# Pwr_Brd1.net
KiCad netlist of a schematic drawn in Altium Designer
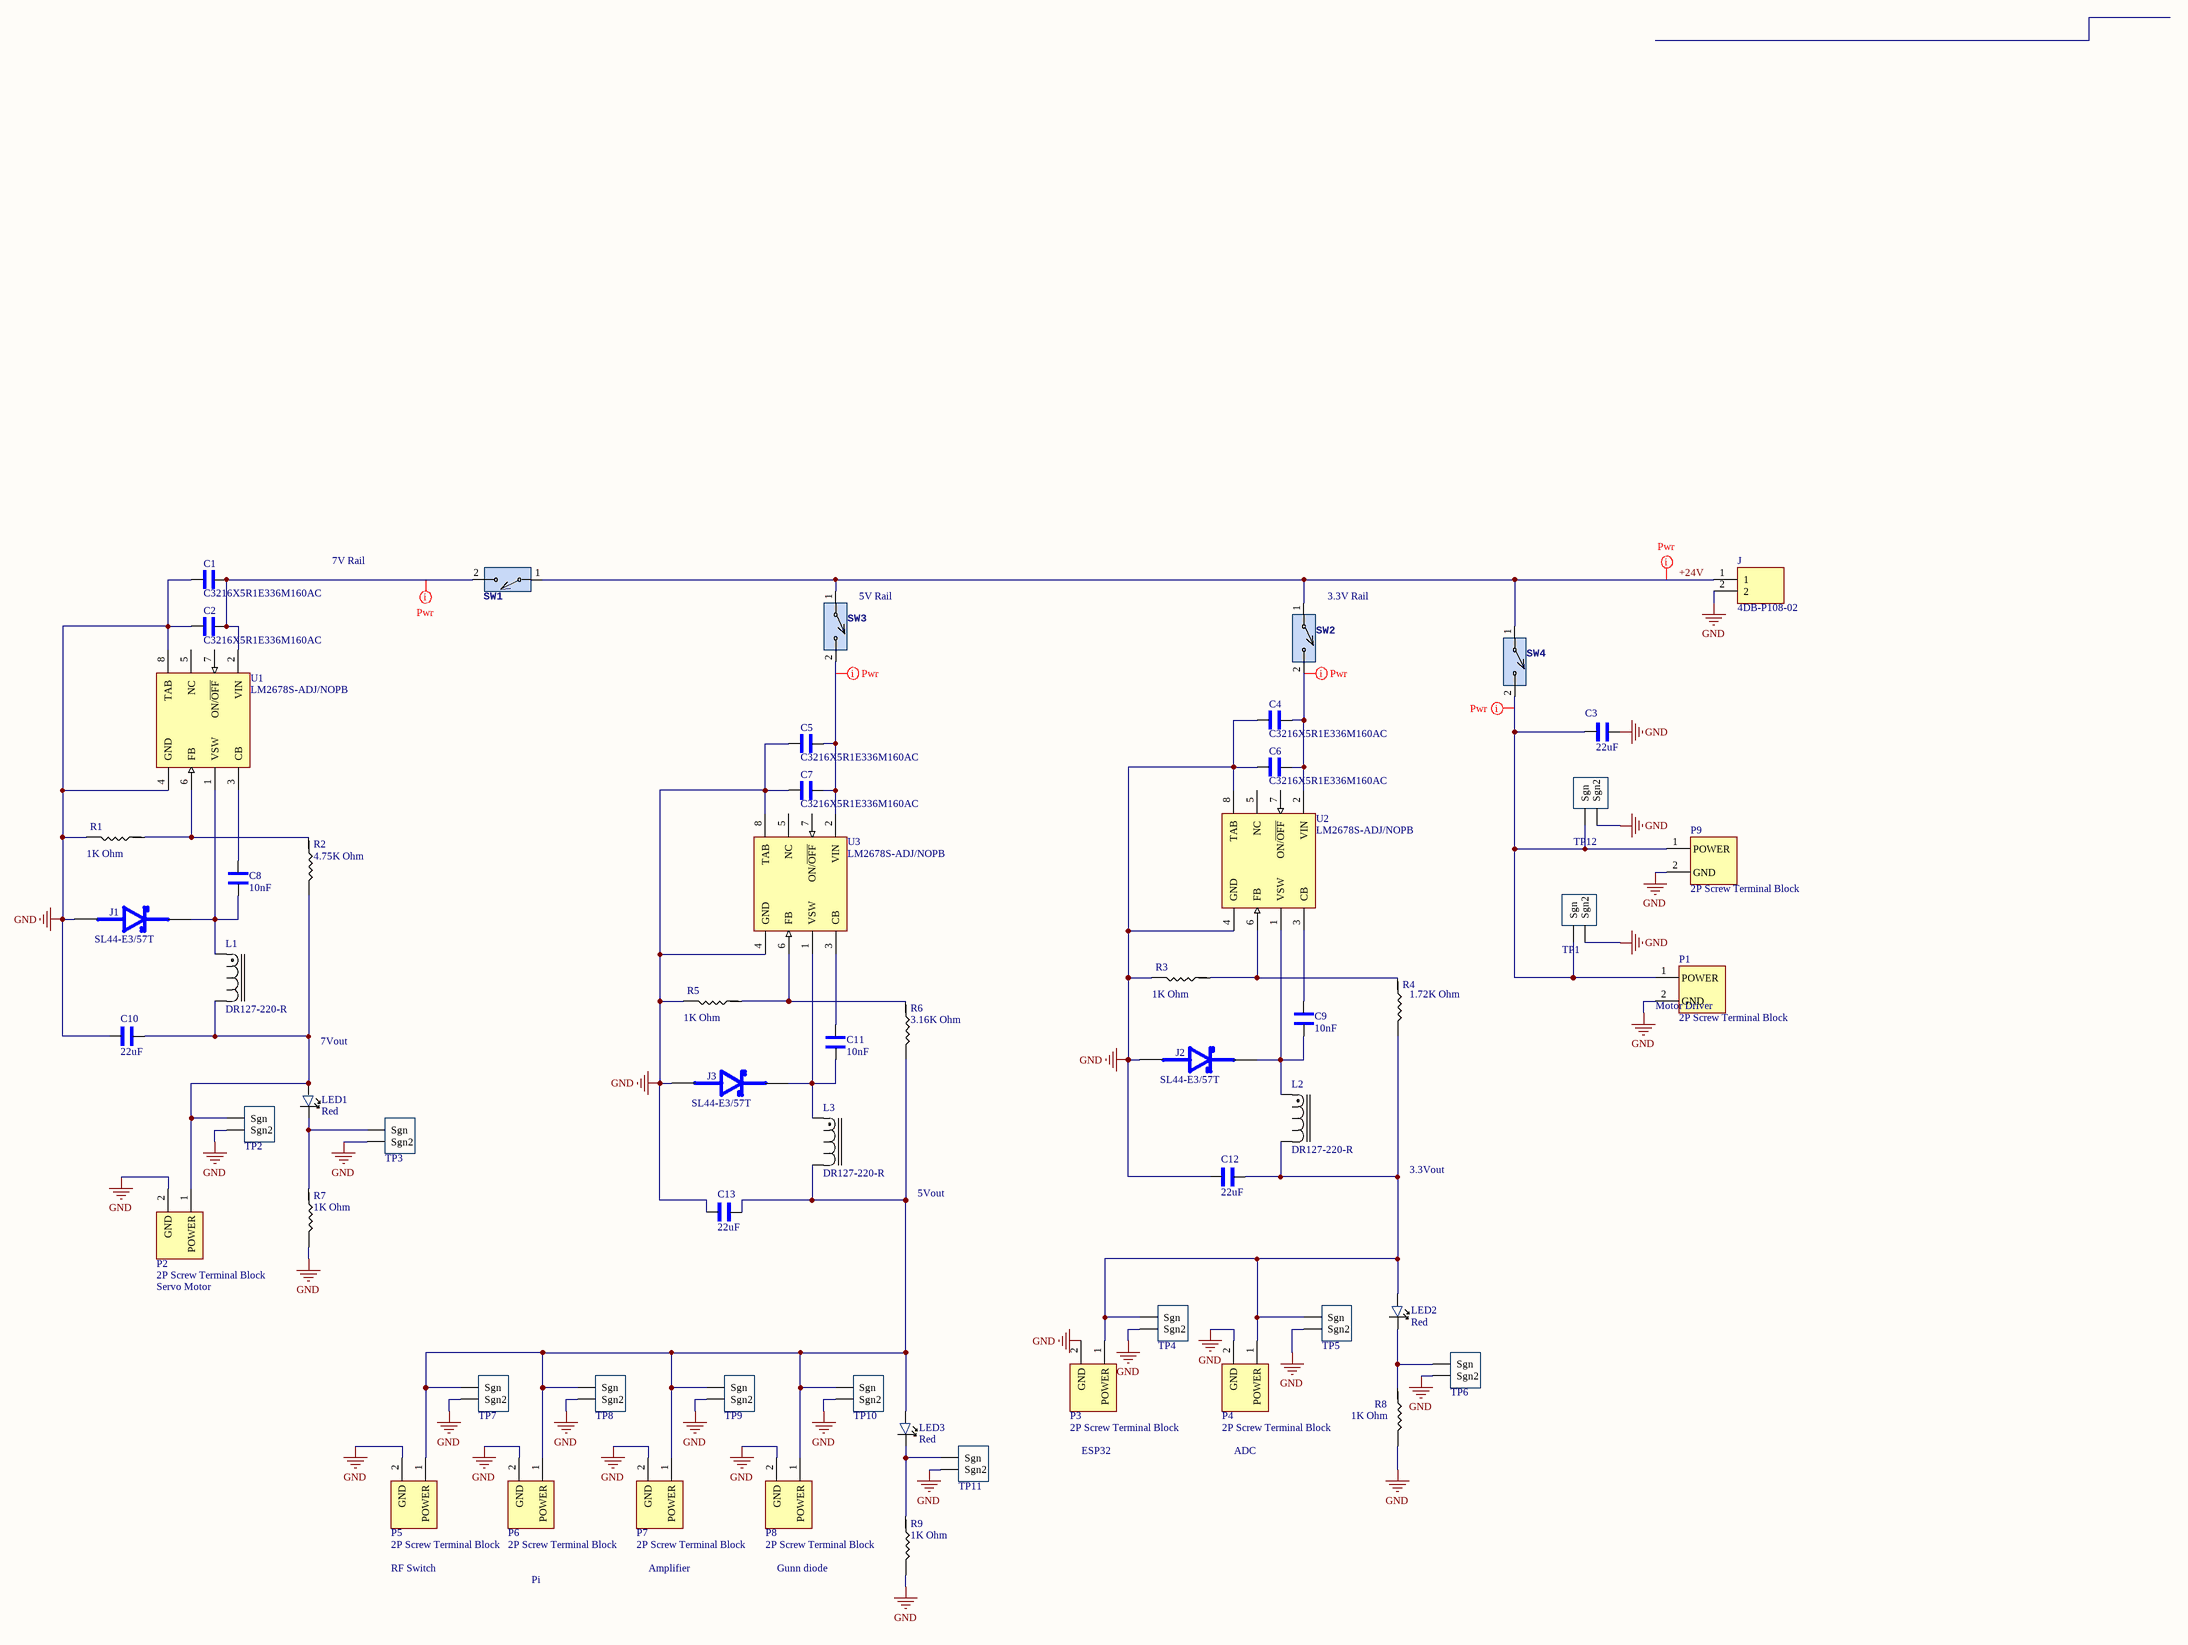
[diagram p0: Pwr_Brd1.SchDoc]

(export (version "E")
  (design (tool "Eeschema 10.0.6"))
  (components
    (comp (ref "C1")
      (value "C3216X5R1E336M160AC")
      (footprint "CAPC3216X180N")
      (description "Cap Ceramic 33uF 25V X5R 20% Pad SMD 1206 85Â°C Low ESR T/R")
      (fields (field (name "MF") "TDK Electronics"))
      (libsource (lib "C3216X5R1E336M160AC") (part "C3216X5R1E336M160AC"))
    )
    (comp (ref "C2")
      (value "C3216X5R1E336M160AC")
      (footprint "CAPC3216X180N")
      (description "Cap Ceramic 33uF 25V X5R 20% Pad SMD 1206 85Â°C Low ESR T/R")
      (fields (field (name "MF") "TDK Electronics"))
      (libsource (lib "C3216X5R1E336M160AC") (part "C3216X5R1E336M160AC"))
    )
    (comp (ref "C3")
      (value "22uF")
      (footprint "1206_Passive_Capacitor")
      (description "22uF ±10% 25V X5R 1206 Multilayer Ceramic Capacitors MLCC - SMD/SMT RoHS")
      (fields (field (name "MFR PART #") "CL31A226KAHNNNE") (field (name "LCSC PART#") "C12891"))
      (libsource (lib "Capstone_Stock_Library") (part "C_22uF_1206"))
    )
    (comp (ref "C4")
      (value "C3216X5R1E336M160AC")
      (footprint "CAPC3216X180N")
      (description "Cap Ceramic 33uF 25V X5R 20% Pad SMD 1206 85Â°C Low ESR T/R")
      (fields (field (name "MF") "TDK Electronics"))
      (libsource (lib "C3216X5R1E336M160AC") (part "C3216X5R1E336M160AC"))
    )
    (comp (ref "C5")
      (value "C3216X5R1E336M160AC")
      (footprint "CAPC3216X180N")
      (description "Cap Ceramic 33uF 25V X5R 20% Pad SMD 1206 85Â°C Low ESR T/R")
      (fields (field (name "MF") "TDK Electronics"))
      (libsource (lib "C3216X5R1E336M160AC") (part "C3216X5R1E336M160AC"))
    )
    (comp (ref "C6")
      (value "C3216X5R1E336M160AC")
      (footprint "CAPC3216X180N")
      (description "Cap Ceramic 33uF 25V X5R 20% Pad SMD 1206 85Â°C Low ESR T/R")
      (fields (field (name "MF") "TDK Electronics"))
      (libsource (lib "C3216X5R1E336M160AC") (part "C3216X5R1E336M160AC"))
    )
    (comp (ref "C7")
      (value "C3216X5R1E336M160AC")
      (footprint "CAPC3216X180N")
      (description "Cap Ceramic 33uF 25V X5R 20% Pad SMD 1206 85Â°C Low ESR T/R")
      (fields (field (name "MF") "TDK Electronics"))
      (libsource (lib "C3216X5R1E336M160AC") (part "C3216X5R1E336M160AC"))
    )
    (comp (ref "C8")
      (value "10nF")
      (footprint "1206_Passive_Capacitor")
      (description "10nF 50V X7R ±10% 1206 Multilayer Ceramic Capacitors MLCC - SMD/SMT ROHS")
      (fields (field (name "MFR PART #") "CL31B105KBHNNNE") (field (name "LCSC PART#") "C1848"))
      (libsource (lib "Capstone_Stock_Library") (part "C_10nF_1206"))
    )
    (comp (ref "C9")
      (value "10nF")
      (footprint "1206_Passive_Capacitor")
      (description "10nF 50V X7R ±10% 1206 Multilayer Ceramic Capacitors MLCC - SMD/SMT ROHS")
      (fields (field (name "MFR PART #") "CL31B105KBHNNNE") (field (name "LCSC PART#") "C1848"))
      (libsource (lib "Capstone_Stock_Library") (part "C_10nF_1206"))
    )
    (comp (ref "C10")
      (value "22uF")
      (footprint "1206_Passive_Capacitor")
      (description "22uF ±10% 25V X5R 1206 Multilayer Ceramic Capacitors MLCC - SMD/SMT RoHS")
      (fields (field (name "MFR PART #") "CL31A226KAHNNNE") (field (name "LCSC PART#") "C12891"))
      (libsource (lib "Capstone_Stock_Library") (part "C_22uF_1206"))
    )
    (comp (ref "C11")
      (value "10nF")
      (footprint "1206_Passive_Capacitor")
      (description "10nF 50V X7R ±10% 1206 Multilayer Ceramic Capacitors MLCC - SMD/SMT ROHS")
      (fields (field (name "MFR PART #") "CL31B105KBHNNNE") (field (name "LCSC PART#") "C1848"))
      (libsource (lib "Capstone_Stock_Library") (part "C_10nF_1206"))
    )
    (comp (ref "C12")
      (value "22uF")
      (footprint "1206_Passive_Capacitor")
      (description "22uF ±10% 25V X5R 1206 Multilayer Ceramic Capacitors MLCC - SMD/SMT RoHS")
      (fields (field (name "MFR PART #") "CL31A226KAHNNNE") (field (name "LCSC PART#") "C12891"))
      (libsource (lib "Capstone_Stock_Library") (part "C_22uF_1206"))
    )
    (comp (ref "C13")
      (value "22uF")
      (footprint "1206_Passive_Capacitor")
      (description "22uF ±10% 25V X5R 1206 Multilayer Ceramic Capacitors MLCC - SMD/SMT RoHS")
      (fields (field (name "MFR PART #") "CL31A226KAHNNNE") (field (name "LCSC PART#") "C12891"))
      (libsource (lib "Capstone_Stock_Library") (part "C_22uF_1206"))
    )
    (comp (ref "J")
      (value "4DB-P108-02")
      (footprint "TE_2-1437667-4")
      (description "Conn; Term Strip; Barrier; 2Pole; 8.26mmPitch; SnglRow; 22-12; Series 4DB; 20A; 150V")
      (fields (field (name "MF") "TE Connectivity"))
      (libsource (lib "4DB-P108-02") (part "4DB-P108-02"))
    )
    (comp (ref "J1")
      (value "SL44-E3/57T")
      (footprint "DIOM7959X262N")
      (description "Diode Schottky 40 V 4A Surface Mount DO-214AB (SMC)")
      (fields (field (name "MF") "Vishay Semiconductor"))
      (libsource (lib "SL44-E3_57T") (part "SL44-E3/57T"))
    )
    (comp (ref "J2")
      (value "SL44-E3/57T")
      (footprint "DIOM7959X262N")
      (description "Diode Schottky 40 V 4A Surface Mount DO-214AB (SMC)")
      (fields (field (name "MF") "Vishay Semiconductor"))
      (libsource (lib "SL44-E3_57T") (part "SL44-E3/57T"))
    )
    (comp (ref "J3")
      (value "SL44-E3/57T")
      (footprint "DIOM7959X262N")
      (description "Diode Schottky 40 V 4A Surface Mount DO-214AB (SMC)")
      (fields (field (name "MF") "Vishay Semiconductor"))
      (libsource (lib "SL44-E3_57T") (part "SL44-E3/57T"))
    )
    (comp (ref "L1")
      (value "DR127-220-R")
      (footprint "DR127")
      (description "Description")
      (fields (field (name "COPYRIGHT") "Copyright (C) 2025 Ultra Librarian. All rights reserved."))
      (libsource (lib "DR127-220-R") (part "DR127-220-R"))
    )
    (comp (ref "L2")
      (value "DR127-220-R")
      (footprint "DR127")
      (description "Description")
      (fields (field (name "COPYRIGHT") "Copyright (C) 2025 Ultra Librarian. All rights reserved."))
      (libsource (lib "DR127-220-R") (part "DR127-220-R"))
    )
    (comp (ref "L3")
      (value "DR127-220-R")
      (footprint "DR127")
      (description "Description")
      (fields (field (name "COPYRIGHT") "Copyright (C) 2025 Ultra Librarian. All rights reserved."))
      (libsource (lib "DR127-220-R") (part "DR127-220-R"))
    )
    (comp (ref "LED1")
      (value "Red")
      (footprint "LED_1206")
      (description "Red 621~631nm 1206 Light Emitting Diodes (LED) RoHS")
      (fields (field (name "MFR PART #") "15-21/R6C-FQ1R1B/2T") (field (name "LCSC PART#") "C93133"))
      (libsource (lib "Capstone_Stock_Library") (part "LED_RED_1206"))
    )
    (comp (ref "LED2")
      (value "Red")
      (footprint "LED_1206")
      (description "Red 621~631nm 1206 Light Emitting Diodes (LED) RoHS")
      (fields (field (name "MFR PART #") "15-21/R6C-FQ1R1B/2T") (field (name "LCSC PART#") "C93133"))
      (libsource (lib "Capstone_Stock_Library") (part "LED_RED_1206"))
    )
    (comp (ref "LED3")
      (value "Red")
      (footprint "LED_1206")
      (description "Red 621~631nm 1206 Light Emitting Diodes (LED) RoHS")
      (fields (field (name "MFR PART #") "15-21/R6C-FQ1R1B/2T") (field (name "LCSC PART#") "C93133"))
      (libsource (lib "Capstone_Stock_Library") (part "LED_RED_1206"))
    )
    (comp (ref "P1")
      (value "2P Screw Terminal Block")
      (footprint "P_Terminal block 3.5mm-pitch")
      (description "Green Straight pin 3.5mm  pitch; P=3.5mm  Screw terminal ROHS")
      (fields (field (name "MFR PART #") "KF350-3.5-2P") (field (name "MANUFACTURER") "Cixi Kefa Elec"))
      (libsource (lib "Capstone_Stock_Library") (part "P_Terminal block"))
    )
    (comp (ref "P2")
      (value "2P Screw Terminal Block")
      (footprint "P_Terminal block 3.5mm-pitch")
      (description "Green Straight pin 3.5mm  pitch; P=3.5mm  Screw terminal ROHS")
      (fields (field (name "MFR PART #") "KF350-3.5-2P") (field (name "MANUFACTURER") "Cixi Kefa Elec"))
      (libsource (lib "") (part "P_Terminal block_1"))
    )
    (comp (ref "P3")
      (value "2P Screw Terminal Block")
      (footprint "P_Terminal block 3.5mm-pitch")
      (description "Green Straight pin 3.5mm  pitch; P=3.5mm  Screw terminal ROHS")
      (fields (field (name "MFR PART #") "KF350-3.5-2P") (field (name "MANUFACTURER") "Cixi Kefa Elec"))
      (libsource (lib "") (part "P_Terminal block_1"))
    )
    (comp (ref "P4")
      (value "2P Screw Terminal Block")
      (footprint "P_Terminal block 3.5mm-pitch")
      (description "Green Straight pin 3.5mm  pitch; P=3.5mm  Screw terminal ROHS")
      (fields (field (name "MFR PART #") "KF350-3.5-2P") (field (name "MANUFACTURER") "Cixi Kefa Elec"))
      (libsource (lib "") (part "P_Terminal block_1"))
    )
    (comp (ref "P5")
      (value "2P Screw Terminal Block")
      (footprint "P_Terminal block 3.5mm-pitch")
      (description "Green Straight pin 3.5mm  pitch; P=3.5mm  Screw terminal ROHS")
      (fields (field (name "MFR PART #") "KF350-3.5-2P") (field (name "MANUFACTURER") "Cixi Kefa Elec"))
      (libsource (lib "") (part "P_Terminal block_1"))
    )
    (comp (ref "P6")
      (value "2P Screw Terminal Block")
      (footprint "P_Terminal block 3.5mm-pitch")
      (description "Green Straight pin 3.5mm  pitch; P=3.5mm  Screw terminal ROHS")
      (fields (field (name "MFR PART #") "KF350-3.5-2P") (field (name "MANUFACTURER") "Cixi Kefa Elec"))
      (libsource (lib "") (part "P_Terminal block_1"))
    )
    (comp (ref "P7")
      (value "2P Screw Terminal Block")
      (footprint "P_Terminal block 3.5mm-pitch")
      (description "Green Straight pin 3.5mm  pitch; P=3.5mm  Screw terminal ROHS")
      (fields (field (name "MFR PART #") "KF350-3.5-2P") (field (name "MANUFACTURER") "Cixi Kefa Elec"))
      (libsource (lib "") (part "P_Terminal block_1"))
    )
    (comp (ref "P8")
      (value "2P Screw Terminal Block")
      (footprint "P_Terminal block 3.5mm-pitch")
      (description "Green Straight pin 3.5mm  pitch; P=3.5mm  Screw terminal ROHS")
      (fields (field (name "MFR PART #") "KF350-3.5-2P") (field (name "MANUFACTURER") "Cixi Kefa Elec"))
      (libsource (lib "") (part "P_Terminal block_1"))
    )
    (comp (ref "P9")
      (value "2P Screw Terminal Block")
      (footprint "P_Terminal block 3.5mm-pitch")
      (description "Green Straight pin 3.5mm  pitch; P=3.5mm  Screw terminal ROHS")
      (fields (field (name "MFR PART #") "KF350-3.5-2P") (field (name "MANUFACTURER") "Cixi Kefa Elec"))
      (libsource (lib "Capstone_Stock_Library") (part "P_Terminal block"))
    )
    (comp (ref "R1")
      (value "1K Ohm")
      (footprint "1206_Passive_Resitor")
      (description "CHIP RESISTOR - SURFACE MOUNT 1KOHMS ±1% 1/4W 1206 ROHS")
      (fields (field (name "MFR PART #") "RNCP1206FTD1K00CT") (field (name "LCSC PART#") "C4410"))
      (libsource (lib "Capstone_Stock_Library") (part "R_1K_1206"))
    )
    (comp (ref "R2")
      (value "4.75K Ohm")
      (footprint "1206_Passive_Resitor")
      (description "CHIP RESISTOR - SURFACE MOUNT 1KOHMS ±1% 1/4W 1206 ROHS")
      (fields (field (name "MFR PART #") "RNCP1206FTD1K00CT") (field (name "LCSC PART#") "C4410"))
      (libsource (lib "Capstone_Stock_Library") (part "R_1K_1206"))
    )
    (comp (ref "R3")
      (value "1K Ohm")
      (footprint "1206_Passive_Resitor")
      (description "CHIP RESISTOR - SURFACE MOUNT 1KOHMS ±1% 1/4W 1206 ROHS")
      (fields (field (name "MFR PART #") "RNCP1206FTD1K00CT") (field (name "LCSC PART#") "C4410"))
      (libsource (lib "Capstone_Stock_Library") (part "R_1K_1206"))
    )
    (comp (ref "R4")
      (value "1.72K Ohm")
      (footprint "1206_Passive_Resitor")
      (description "CHIP RESISTOR - SURFACE MOUNT 1KOHMS ±1% 1/4W 1206 ROHS")
      (fields (field (name "MFR PART #") "RNCP1206FTD1K00CT") (field (name "LCSC PART#") "C4410"))
      (libsource (lib "Capstone_Stock_Library") (part "R_1K_1206"))
    )
    (comp (ref "R5")
      (value "1K Ohm")
      (footprint "1206_Passive_Resitor")
      (description "CHIP RESISTOR - SURFACE MOUNT 1KOHMS ±1% 1/4W 1206 ROHS")
      (fields (field (name "MFR PART #") "RNCP1206FTD1K00CT") (field (name "LCSC PART#") "C4410"))
      (libsource (lib "Capstone_Stock_Library") (part "R_1K_1206"))
    )
    (comp (ref "R6")
      (value "3.16K Ohm")
      (footprint "1206_Passive_Resitor")
      (description "CHIP RESISTOR - SURFACE MOUNT 1KOHMS ±1% 1/4W 1206 ROHS")
      (fields (field (name "MFR PART #") "RNCP1206FTD1K00CT") (field (name "LCSC PART#") "C4410"))
      (libsource (lib "Capstone_Stock_Library") (part "R_1K_1206"))
    )
    (comp (ref "R7")
      (value "1K Ohm")
      (footprint "1206_Passive_Resitor")
      (description "CHIP RESISTOR - SURFACE MOUNT 1KOHMS ±1% 1/4W 1206 ROHS")
      (fields (field (name "MFR PART #") "RNCP1206FTD1K00CT") (field (name "LCSC PART#") "C4410"))
      (libsource (lib "Capstone_Stock_Library") (part "R_1K_1206"))
    )
    (comp (ref "R8")
      (value "1K Ohm")
      (footprint "1206_Passive_Resitor")
      (description "CHIP RESISTOR - SURFACE MOUNT 1KOHMS ±1% 1/4W 1206 ROHS")
      (fields (field (name "MFR PART #") "RNCP1206FTD1K00CT") (field (name "LCSC PART#") "C4410"))
      (libsource (lib "Capstone_Stock_Library") (part "R_1K_1206"))
    )
    (comp (ref "R9")
      (value "1K Ohm")
      (footprint "1206_Passive_Resitor")
      (description "CHIP RESISTOR - SURFACE MOUNT 1KOHMS ±1% 1/4W 1206 ROHS")
      (fields (field (name "MFR PART #") "RNCP1206FTD1K00CT") (field (name "LCSC PART#") "C4410"))
      (libsource (lib "Capstone_Stock_Library") (part "R_1K_1206"))
    )
    (comp (ref "SW1")
      (value "SW_2Pin_100mil_Switch")
      (footprint "2Pin-Header-Conn")
      (description "2Pin Header")
      (fields (field (name "LCSC PART#") "C124375"))
      (libsource (lib "Capstone_Stock_Library") (part "SW_2Pin_100mil_Switch"))
    )
    (comp (ref "SW2")
      (value "SW_2Pin_100mil_Switch")
      (footprint "2Pin-Header-Conn")
      (description "2Pin Header")
      (fields (field (name "LCSC PART#") "C124375"))
      (libsource (lib "") (part "SW_2Pin_100mil_Switch_1"))
    )
    (comp (ref "SW3")
      (value "SW_2Pin_100mil_Switch")
      (footprint "2Pin-Header-Conn")
      (description "2Pin Header")
      (fields (field (name "LCSC PART#") "C124375"))
      (libsource (lib "") (part "SW_2Pin_100mil_Switch_1"))
    )
    (comp (ref "SW4")
      (value "SW_2Pin_100mil_Switch")
      (footprint "2Pin-Header-Conn")
      (description "2Pin Header")
      (fields (field (name "LCSC PART#") "C124375"))
      (libsource (lib "") (part "SW_2Pin_100mil_Switch_1"))
    )
    (comp (ref "TP1")
      (value "10x Probe TP")
      (footprint "TP_Diff_Probe")
      (description "Test Point 300 mil centers")
      (libsource (lib "") (part "TP_Diff_Probe_1"))
    )
    (comp (ref "TP2")
      (value "10x Probe TP")
      (footprint "TP_Diff_Probe")
      (description "Test Point 300 mil centers")
      (libsource (lib "Capstone_Stock_Library") (part "TP_Diff_Probe"))
    )
    (comp (ref "TP3")
      (value "10x Probe TP")
      (footprint "TP_Diff_Probe")
      (description "Test Point 300 mil centers")
      (libsource (lib "Capstone_Stock_Library") (part "TP_Diff_Probe"))
    )
    (comp (ref "TP4")
      (value "10x Probe TP")
      (footprint "TP_Diff_Probe")
      (description "Test Point 300 mil centers")
      (libsource (lib "Capstone_Stock_Library") (part "TP_Diff_Probe"))
    )
    (comp (ref "TP5")
      (value "10x Probe TP")
      (footprint "TP_Diff_Probe")
      (description "Test Point 300 mil centers")
      (libsource (lib "Capstone_Stock_Library") (part "TP_Diff_Probe"))
    )
    (comp (ref "TP6")
      (value "10x Probe TP")
      (footprint "TP_Diff_Probe")
      (description "Test Point 300 mil centers")
      (libsource (lib "Capstone_Stock_Library") (part "TP_Diff_Probe"))
    )
    (comp (ref "TP7")
      (value "10x Probe TP")
      (footprint "TP_Diff_Probe")
      (description "Test Point 300 mil centers")
      (libsource (lib "Capstone_Stock_Library") (part "TP_Diff_Probe"))
    )
    (comp (ref "TP8")
      (value "10x Probe TP")
      (footprint "TP_Diff_Probe")
      (description "Test Point 300 mil centers")
      (libsource (lib "Capstone_Stock_Library") (part "TP_Diff_Probe"))
    )
    (comp (ref "TP9")
      (value "10x Probe TP")
      (footprint "TP_Diff_Probe")
      (description "Test Point 300 mil centers")
      (libsource (lib "Capstone_Stock_Library") (part "TP_Diff_Probe"))
    )
    (comp (ref "TP10")
      (value "10x Probe TP")
      (footprint "TP_Diff_Probe")
      (description "Test Point 300 mil centers")
      (libsource (lib "Capstone_Stock_Library") (part "TP_Diff_Probe"))
    )
    (comp (ref "TP11")
      (value "10x Probe TP")
      (footprint "TP_Diff_Probe")
      (description "Test Point 300 mil centers")
      (libsource (lib "Capstone_Stock_Library") (part "TP_Diff_Probe"))
    )
    (comp (ref "TP12")
      (value "10x Probe TP")
      (footprint "TP_Diff_Probe")
      (description "Test Point 300 mil centers")
      (libsource (lib "") (part "TP_Diff_Probe_1"))
    )
    (comp (ref "U1")
      (value "LM2678S-ADJ/NOPB")
      (footprint "KTW0007B_N")
      (description "SIMPLE SWITCHER® High Efficiency 5A Step-Down Voltage Regulator, 7-pin TO-263, Pb-Free")
      (fields (field (name "MANUFACTURER") "Texas Instruments"))
      (libsource (lib "Altium Content Vault") (part "PM-REG-LM2678S"))
    )
    (comp (ref "U2")
      (value "LM2678S-ADJ/NOPB")
      (footprint "KTW0007B_N")
      (description "SIMPLE SWITCHER® High Efficiency 5A Step-Down Voltage Regulator, 7-pin TO-263, Pb-Free")
      (fields (field (name "MANUFACTURER") "Texas Instruments"))
      (libsource (lib "Altium Content Vault") (part "PM-REG-LM2678S"))
    )
    (comp (ref "U3")
      (value "LM2678S-ADJ/NOPB")
      (footprint "KTW0007B_N")
      (description "SIMPLE SWITCHER® High Efficiency 5A Step-Down Voltage Regulator, 7-pin TO-263, Pb-Free")
      (fields (field (name "MANUFACTURER") "Texas Instruments"))
      (libsource (lib "Altium Content Vault") (part "PM-REG-LM2678S"))
    )
  )
  (nets
    (net (code "1") (name "/+24V") (class "Default")
      (node (ref "J") (pin "1") (pinfunction "1_1") (pintype "passive"))
      (node (ref "SW1") (pin "1") (pinfunction "1_1") (pintype "passive"))
      (node (ref "SW2") (pin "1") (pinfunction "1_1") (pintype "passive"))
      (node (ref "SW3") (pin "1") (pinfunction "1_1") (pintype "passive"))
      (node (ref "SW4") (pin "1") (pinfunction "1_1") (pintype "passive"))
    )
    (net (code "2") (name "GND") (class "Default")
      (node (ref "C1") (pin "1") (pinfunction "1_1") (pintype "passive"))
      (node (ref "C10") (pin "1") (pinfunction "1_1") (pintype "passive"))
      (node (ref "C12") (pin "1") (pinfunction "1_1") (pintype "passive"))
      (node (ref "C13") (pin "1") (pinfunction "1_1") (pintype "passive"))
      (node (ref "C2") (pin "1") (pinfunction "1_1") (pintype "passive"))
      (node (ref "C3") (pin "2") (pinfunction "2_2") (pintype "passive"))
      (node (ref "C4") (pin "1") (pinfunction "1_1") (pintype "passive"))
      (node (ref "C5") (pin "1") (pinfunction "1_1") (pintype "passive"))
      (node (ref "C6") (pin "1") (pinfunction "1_1") (pintype "passive"))
      (node (ref "C7") (pin "1") (pinfunction "1_1") (pintype "passive"))
      (node (ref "J") (pin "2") (pinfunction "2_2") (pintype "passive"))
      (node (ref "J1") (pin "A") (pinfunction "A_A") (pintype "passive"))
      (node (ref "J2") (pin "A") (pinfunction "A_A") (pintype "passive"))
      (node (ref "J3") (pin "A") (pinfunction "A_A") (pintype "passive"))
      (node (ref "P1") (pin "2") (pinfunction "GND_2") (pintype "passive"))
      (node (ref "P2") (pin "2") (pinfunction "GND_2") (pintype "passive"))
      (node (ref "P3") (pin "2") (pinfunction "GND_2") (pintype "passive"))
      (node (ref "P4") (pin "2") (pinfunction "GND_2") (pintype "passive"))
      (node (ref "P5") (pin "2") (pinfunction "GND_2") (pintype "passive"))
      (node (ref "P6") (pin "2") (pinfunction "GND_2") (pintype "passive"))
      (node (ref "P7") (pin "2") (pinfunction "GND_2") (pintype "passive"))
      (node (ref "P8") (pin "2") (pinfunction "GND_2") (pintype "passive"))
      (node (ref "P9") (pin "2") (pinfunction "GND_2") (pintype "passive"))
      (node (ref "R1") (pin "2") (pinfunction "2_2") (pintype "passive"))
      (node (ref "R3") (pin "2") (pinfunction "2_2") (pintype "passive"))
      (node (ref "R5") (pin "2") (pinfunction "2_2") (pintype "passive"))
      (node (ref "R7") (pin "2") (pinfunction "2_2") (pintype "passive"))
      (node (ref "R8") (pin "2") (pinfunction "2_2") (pintype "passive"))
      (node (ref "R9") (pin "2") (pinfunction "2_2") (pintype "passive"))
      (node (ref "TP1") (pin "2") (pinfunction "Sgn2_2") (pintype "passive"))
      (node (ref "TP10") (pin "2") (pinfunction "Sgn2_2") (pintype "passive"))
      (node (ref "TP11") (pin "2") (pinfunction "Sgn2_2") (pintype "passive"))
      (node (ref "TP12") (pin "2") (pinfunction "Sgn2_2") (pintype "passive"))
      (node (ref "TP2") (pin "2") (pinfunction "Sgn2_2") (pintype "passive"))
      (node (ref "TP3") (pin "2") (pinfunction "Sgn2_2") (pintype "passive"))
      (node (ref "TP4") (pin "2") (pinfunction "Sgn2_2") (pintype "passive"))
      (node (ref "TP5") (pin "2") (pinfunction "Sgn2_2") (pintype "passive"))
      (node (ref "TP6") (pin "2") (pinfunction "Sgn2_2") (pintype "passive"))
      (node (ref "TP7") (pin "2") (pinfunction "Sgn2_2") (pintype "passive"))
      (node (ref "TP8") (pin "2") (pinfunction "Sgn2_2") (pintype "passive"))
      (node (ref "TP9") (pin "2") (pinfunction "Sgn2_2") (pintype "passive"))
      (node (ref "U1") (pin "4") (pinfunction "GND_4") (pintype "power_in"))
      (node (ref "U1") (pin "8") (pinfunction "TAB_8") (pintype "power_in"))
      (node (ref "U2") (pin "4") (pinfunction "GND_4") (pintype "power_in"))
      (node (ref "U2") (pin "8") (pinfunction "TAB_8") (pintype "power_in"))
      (node (ref "U3") (pin "4") (pinfunction "GND_4") (pintype "power_in"))
      (node (ref "U3") (pin "8") (pinfunction "TAB_8") (pintype "power_in"))
    )
    (net (code "3") (name "Net-(P1-POWER)") (class "Default")
      (node (ref "C3") (pin "1") (pinfunction "1_1") (pintype "passive"))
      (node (ref "P1") (pin "1") (pinfunction "POWER_1") (pintype "passive"))
      (node (ref "P9") (pin "1") (pinfunction "POWER_1") (pintype "passive"))
      (node (ref "SW4") (pin "2") (pinfunction "2_2") (pintype "passive"))
      (node (ref "TP1") (pin "1") (pinfunction "Sgn_1") (pintype "passive"))
      (node (ref "TP12") (pin "1") (pinfunction "Sgn_1") (pintype "passive"))
    )
    (net (code "4") (name "Net-(P2-POWER)") (class "Default")
      (node (ref "C10") (pin "2") (pinfunction "2_2") (pintype "passive"))
      (node (ref "L1") (pin "2") (pinfunction "2_2") (pintype "passive"))
      (node (ref "LED1") (pin "1") (pinfunction "1_1") (pintype "passive"))
      (node (ref "P2") (pin "1") (pinfunction "POWER_1") (pintype "passive"))
      (node (ref "R2") (pin "2") (pinfunction "2_2") (pintype "passive"))
      (node (ref "TP2") (pin "1") (pinfunction "Sgn_1") (pintype "passive"))
    )
    (net (code "5") (name "Net-(P3-POWER)") (class "Default")
      (node (ref "C12") (pin "2") (pinfunction "2_2") (pintype "passive"))
      (node (ref "L2") (pin "2") (pinfunction "2_2") (pintype "passive"))
      (node (ref "LED2") (pin "1") (pinfunction "1_1") (pintype "passive"))
      (node (ref "P3") (pin "1") (pinfunction "POWER_1") (pintype "passive"))
      (node (ref "P4") (pin "1") (pinfunction "POWER_1") (pintype "passive"))
      (node (ref "R4") (pin "2") (pinfunction "2_2") (pintype "passive"))
      (node (ref "TP4") (pin "1") (pinfunction "Sgn_1") (pintype "passive"))
      (node (ref "TP5") (pin "1") (pinfunction "Sgn_1") (pintype "passive"))
    )
    (net (code "6") (name "Net-(P5-POWER)") (class "Default")
      (node (ref "C13") (pin "2") (pinfunction "2_2") (pintype "passive"))
      (node (ref "L3") (pin "2") (pinfunction "2_2") (pintype "passive"))
      (node (ref "LED3") (pin "1") (pinfunction "1_1") (pintype "passive"))
      (node (ref "P5") (pin "1") (pinfunction "POWER_1") (pintype "passive"))
      (node (ref "P6") (pin "1") (pinfunction "POWER_1") (pintype "passive"))
      (node (ref "P7") (pin "1") (pinfunction "POWER_1") (pintype "passive"))
      (node (ref "P8") (pin "1") (pinfunction "POWER_1") (pintype "passive"))
      (node (ref "R6") (pin "2") (pinfunction "2_2") (pintype "passive"))
      (node (ref "TP10") (pin "1") (pinfunction "Sgn_1") (pintype "passive"))
      (node (ref "TP7") (pin "1") (pinfunction "Sgn_1") (pintype "passive"))
      (node (ref "TP8") (pin "1") (pinfunction "Sgn_1") (pintype "passive"))
      (node (ref "TP9") (pin "1") (pinfunction "Sgn_1") (pintype "passive"))
    )
    (net (code "7") (name "Net-(TP3-Sgn)") (class "Default")
      (node (ref "LED1") (pin "2") (pinfunction "2_2") (pintype "passive"))
      (node (ref "R7") (pin "1") (pinfunction "1_1") (pintype "passive"))
      (node (ref "TP3") (pin "1") (pinfunction "Sgn_1") (pintype "passive"))
    )
    (net (code "8") (name "Net-(TP6-Sgn)") (class "Default")
      (node (ref "LED2") (pin "2") (pinfunction "2_2") (pintype "passive"))
      (node (ref "R8") (pin "1") (pinfunction "1_1") (pintype "passive"))
      (node (ref "TP6") (pin "1") (pinfunction "Sgn_1") (pintype "passive"))
    )
    (net (code "9") (name "Net-(TP11-Sgn)") (class "Default")
      (node (ref "LED3") (pin "2") (pinfunction "2_2") (pintype "passive"))
      (node (ref "R9") (pin "1") (pinfunction "1_1") (pintype "passive"))
      (node (ref "TP11") (pin "1") (pinfunction "Sgn_1") (pintype "passive"))
    )
    (net (code "10") (name "Net-(U1-CB)") (class "Default")
      (node (ref "C8") (pin "2") (pinfunction "2_2") (pintype "passive"))
      (node (ref "U1") (pin "3") (pinfunction "CB_3") (pintype "passive"))
    )
    (net (code "11") (name "Net-(U1-FB)") (class "Default")
      (node (ref "R1") (pin "1") (pinfunction "1_1") (pintype "passive"))
      (node (ref "R2") (pin "1") (pinfunction "1_1") (pintype "passive"))
      (node (ref "U1") (pin "6") (pinfunction "FB_6") (pintype "input"))
    )
    (net (code "12") (name "Net-(U1-VIN)") (class "Default")
      (node (ref "C1") (pin "2") (pinfunction "2_2") (pintype "passive"))
      (node (ref "C2") (pin "2") (pinfunction "2_2") (pintype "passive"))
      (node (ref "SW1") (pin "2") (pinfunction "2_2") (pintype "passive"))
      (node (ref "U1") (pin "2") (pinfunction "VIN_2") (pintype "power_in"))
    )
    (net (code "13") (name "Net-(U1-VSW)") (class "Default")
      (node (ref "C8") (pin "1") (pinfunction "1_1") (pintype "passive"))
      (node (ref "J1") (pin "C") (pinfunction "C_C") (pintype "passive"))
      (node (ref "L1") (pin "1") (pinfunction "1_1") (pintype "passive"))
      (node (ref "U1") (pin "1") (pinfunction "VSW_1") (pintype "power_in"))
    )
    (net (code "14") (name "Net-(U2-CB)") (class "Default")
      (node (ref "C9") (pin "2") (pinfunction "2_2") (pintype "passive"))
      (node (ref "U2") (pin "3") (pinfunction "CB_3") (pintype "passive"))
    )
    (net (code "15") (name "Net-(U2-FB)") (class "Default")
      (node (ref "R3") (pin "1") (pinfunction "1_1") (pintype "passive"))
      (node (ref "R4") (pin "1") (pinfunction "1_1") (pintype "passive"))
      (node (ref "U2") (pin "6") (pinfunction "FB_6") (pintype "input"))
    )
    (net (code "16") (name "Net-(U2-VIN)") (class "Default")
      (node (ref "C4") (pin "2") (pinfunction "2_2") (pintype "passive"))
      (node (ref "C6") (pin "2") (pinfunction "2_2") (pintype "passive"))
      (node (ref "SW2") (pin "2") (pinfunction "2_2") (pintype "passive"))
      (node (ref "U2") (pin "2") (pinfunction "VIN_2") (pintype "power_in"))
    )
    (net (code "17") (name "Net-(U2-VSW)") (class "Default")
      (node (ref "C9") (pin "1") (pinfunction "1_1") (pintype "passive"))
      (node (ref "J2") (pin "C") (pinfunction "C_C") (pintype "passive"))
      (node (ref "L2") (pin "1") (pinfunction "1_1") (pintype "passive"))
      (node (ref "U2") (pin "1") (pinfunction "VSW_1") (pintype "power_in"))
    )
    (net (code "18") (name "Net-(U3-CB)") (class "Default")
      (node (ref "C11") (pin "2") (pinfunction "2_2") (pintype "passive"))
      (node (ref "U3") (pin "3") (pinfunction "CB_3") (pintype "passive"))
    )
    (net (code "19") (name "Net-(U3-FB)") (class "Default")
      (node (ref "R5") (pin "1") (pinfunction "1_1") (pintype "passive"))
      (node (ref "R6") (pin "1") (pinfunction "1_1") (pintype "passive"))
      (node (ref "U3") (pin "6") (pinfunction "FB_6") (pintype "input"))
    )
    (net (code "20") (name "Net-(U3-VIN)") (class "Default")
      (node (ref "C5") (pin "2") (pinfunction "2_2") (pintype "passive"))
      (node (ref "C7") (pin "2") (pinfunction "2_2") (pintype "passive"))
      (node (ref "SW3") (pin "2") (pinfunction "2_2") (pintype "passive"))
      (node (ref "U3") (pin "2") (pinfunction "VIN_2") (pintype "power_in"))
    )
    (net (code "21") (name "Net-(U3-VSW)") (class "Default")
      (node (ref "C11") (pin "1") (pinfunction "1_1") (pintype "passive"))
      (node (ref "J3") (pin "C") (pinfunction "C_C") (pintype "passive"))
      (node (ref "L3") (pin "1") (pinfunction "1_1") (pintype "passive"))
      (node (ref "U3") (pin "1") (pinfunction "VSW_1") (pintype "power_in"))
    )
    (net (code "22") (name "unconnected-(U1-NC-Pad5)") (class "Default")
      (node (ref "U1") (pin "5") (pinfunction "NC_5") (pintype "passive"))
    )
    (net (code "23") (name "unconnected-(U1-ON{slash}~{OFF}-Pad7)") (class "Default")
      (node (ref "U1") (pin "7") (pinfunction "ON/~{OFF}_7") (pintype "input"))
    )
    (net (code "24") (name "unconnected-(U2-NC-Pad5)") (class "Default")
      (node (ref "U2") (pin "5") (pinfunction "NC_5") (pintype "passive"))
    )
    (net (code "25") (name "unconnected-(U2-ON{slash}~{OFF}-Pad7)") (class "Default")
      (node (ref "U2") (pin "7") (pinfunction "ON/~{OFF}_7") (pintype "input"))
    )
    (net (code "26") (name "unconnected-(U3-NC-Pad5)") (class "Default")
      (node (ref "U3") (pin "5") (pinfunction "NC_5") (pintype "passive"))
    )
    (net (code "27") (name "unconnected-(U3-ON{slash}~{OFF}-Pad7)") (class "Default")
      (node (ref "U3") (pin "7") (pinfunction "ON/~{OFF}_7") (pintype "input"))
    )
  )
)
